# Power.net
KiCad netlist of a schematic drawn in Altium Designer
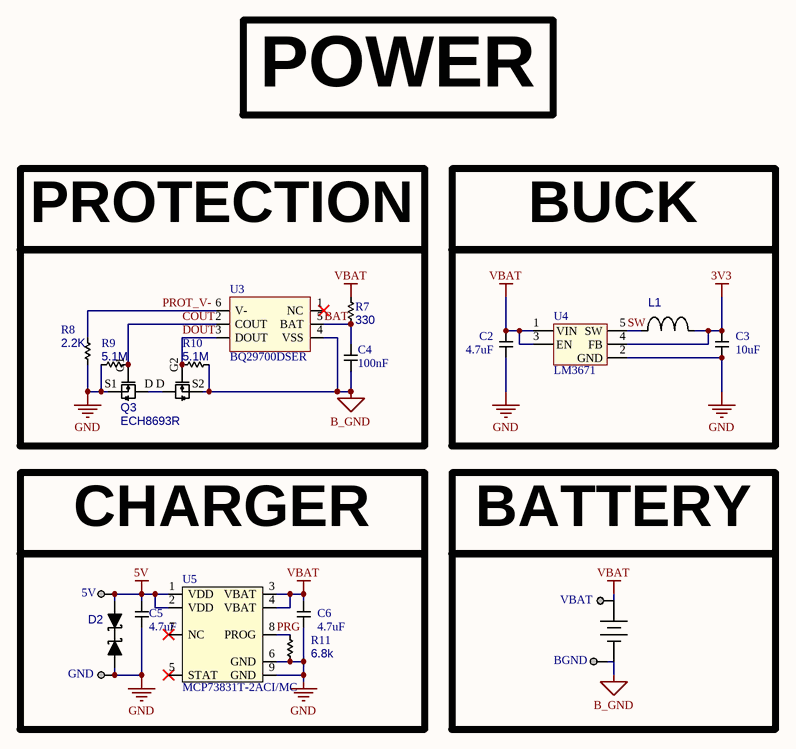
[diagram p0: Power.SchDoc]

(export (version "E")
  (design (tool "Eeschema 10.0.6"))
  (components
    (comp (ref "5V")
      (value "0.1\" Header")
      (footprint "0.1\" Header")
      (libsource (lib "smLib") (part "0.1{dblquote} Header"))
    )
    (comp (ref "BGND")
      (value "0.1\" Header")
      (footprint "0.1\" Header")
      (libsource (lib "smLib") (part "0.1{dblquote} Header"))
    )
    (comp (ref "C2")
      (value "4.7uF")
      (footprint "CAP_0402_HIGH")
      (description "0402 Capacitor")
      (libsource (lib "smLib") (part "Capacitor_0402"))
    )
    (comp (ref "C3")
      (value "10uF")
      (footprint "CAP_0402_HIGH")
      (description "0402 Capacitor")
      (libsource (lib "smLib") (part "Capacitor_0402"))
    )
    (comp (ref "C4")
      (value "100nF")
      (footprint "CAP_0402_HIGH")
      (description "0402 Capacitor")
      (libsource (lib "smLib") (part "Capacitor_0402"))
    )
    (comp (ref "C5")
      (value "4.7uF")
      (footprint "CAP_0402_HIGH")
      (description "0402 Capacitor")
      (libsource (lib "smLib") (part "Capacitor_0402"))
    )
    (comp (ref "C6")
      (value "4.7uF")
      (footprint "CAP_0402_HIGH")
      (description "0402 Capacitor")
      (libsource (lib "smLib") (part "Capacitor_0402"))
    )
    (comp (ref "D2")
      (value "D5V0L1B2LP4-7B")
      (footprint "D5V0L1B2LP4-7B")
      (description "D5V0L1B2LP4-7B 14V Clamp 6A (8/20µs) Ipp Tvs Diode Surface Mount X2-DFN1006-2")
      (libsource (lib "smLib") (part "D5V0L1B2LP4-7B"))
    )
    (comp (ref "GND")
      (value "0.1\" Header")
      (footprint "0.1\" Header")
      (libsource (lib "smLib") (part "0.1{dblquote} Header"))
    )
    (comp (ref "L1")
      (value "CIGT201610EH2R2MNE")
      (footprint "CIGT201610EH2R2MNE")
      (description "CIGT201610EH2R2MNE 2.2µH Unshielded Thin Film Inductor 2.5A 87mOhm Max 0806 (2016 Metric)")
      (libsource (lib "smLib") (part "CIGT201610EH2R2MNE"))
    )
    (comp (ref "Q3")
      (value "ECH8693R")
      (footprint "ECH8693R")
      (description "Mosfet Array 2 N-Channel (Dual) Common Drain 24V 14A 1.4W Surface Mount SOT-28FL/ECH8")
      (libsource (lib "smLib") (part "ECH8693R"))
    )
    (comp (ref "R7")
      (value "330")
      (footprint "RES_0402_HIGH")
      (description "0402 Resistor")
      (libsource (lib "smLib") (part "Resistor_0402"))
    )
    (comp (ref "R8")
      (value "2.2K")
      (footprint "RES_0402_HIGH")
      (description "0402 Resistor")
      (libsource (lib "smLib") (part "Resistor_0402"))
    )
    (comp (ref "R9")
      (value "5.1M")
      (footprint "RES_0402_HIGH")
      (description "0402 Resistor")
      (libsource (lib "smLib") (part "Resistor_0402"))
    )
    (comp (ref "R10")
      (value "5.1M")
      (footprint "RES_0402_HIGH")
      (description "0402 Resistor")
      (libsource (lib "smLib") (part "Resistor_0402"))
    )
    (comp (ref "R11")
      (value "6.8k")
      (footprint "RES_0402_HIGH")
      (description "0402 Resistor")
      (libsource (lib "smLib") (part "Resistor_0402"))
    )
    (comp (ref "U3")
      (value "BQ29700DSER")
      (footprint "BQ29700DSER")
      (description "Battery Battery Protection IC Lithium-Ion/Polymer 6-WSON (1.5x1.5)")
      (libsource (lib "smLib") (part "BQ29700DSER"))
    )
    (comp (ref "U4")
      (value "LM3671")
      (footprint "LM3671-BGA")
      (description "LM3671 IC REG BUCK 3.3V 0.6A SYNC 5USMD")
      (libsource (lib "smLib") (part "LM3671"))
    )
    (comp (ref "U5")
      (value "MCP73831T-2ACI/MC")
      (footprint "MCP73831T-2ACI/MC")
      (description "MCP73831T-2ACI/MC Charger IC Lithium-Ion/Polymer")
      (libsource (lib "smLib") (part "MCP73831T-2ACI/MC"))
    )
    (comp (ref "VBAT")
      (value "0.1\" Header")
      (footprint "0.1\" Header")
      (libsource (lib "smLib") (part "0.1{dblquote} Header"))
    )
  )
  (nets
    (net (code "1") (name "/BAT") (class "Default")
      (node (ref "C4") (pin "2") (pinfunction "2_2") (pintype "passive"))
      (node (ref "R7") (pin "2") (pinfunction "2_2") (pintype "passive"))
      (node (ref "U3") (pin "5") (pinfunction "BAT_5") (pintype "passive"))
    )
    (net (code "2") (name "/COUT") (class "Default")
      (node (ref "Q3") (pin "G1") (pinfunction "G_G1") (pintype "passive"))
      (node (ref "R9") (pin "1") (pinfunction "1_1") (pintype "passive"))
      (node (ref "U3") (pin "2") (pinfunction "COUT_2") (pintype "passive"))
    )
    (net (code "3") (name "/DOUT") (class "Default")
      (node (ref "Q3") (pin "G2") (pinfunction "G_G2") (pintype "passive"))
      (node (ref "R10") (pin "2") (pinfunction "2_2") (pintype "passive"))
      (node (ref "U3") (pin "3") (pinfunction "DOUT_3") (pintype "passive"))
    )
    (net (code "4") (name "/PRG") (class "Default")
      (node (ref "R11") (pin "1") (pinfunction "1_1") (pintype "passive"))
      (node (ref "U5") (pin "8") (pinfunction "PROG_8") (pintype "passive"))
    )
    (net (code "5") (name "/PROT_V-") (class "Default")
      (node (ref "R8") (pin "2") (pinfunction "2_2") (pintype "passive"))
      (node (ref "U3") (pin "6") (pinfunction "V-_6") (pintype "passive"))
    )
    (net (code "6") (name "/SW") (class "Default")
      (node (ref "L1") (pin "1") (pinfunction "1_1") (pintype "passive"))
      (node (ref "U4") (pin "5") (pinfunction "SW_5") (pintype "passive"))
    )
    (net (code "7") (name "3V3") (class "Default")
      (node (ref "C3") (pin "2") (pinfunction "2_2") (pintype "passive"))
      (node (ref "L1") (pin "2") (pinfunction "2_2") (pintype "passive"))
      (node (ref "U4") (pin "4") (pinfunction "FB_4") (pintype "passive"))
    )
    (net (code "8") (name "5V") (class "Default")
      (node (ref "5V") (pin "1") (pinfunction "1_1") (pintype "passive"))
      (node (ref "C5") (pin "2") (pinfunction "2_2") (pintype "passive"))
      (node (ref "D2") (pin "1") (pinfunction "1_1") (pintype "passive"))
      (node (ref "U5") (pin "1") (pinfunction "VDD_1") (pintype "passive"))
      (node (ref "U5") (pin "2") (pinfunction "VDD_2") (pintype "passive"))
    )
    (net (code "9") (name "B_GND") (class "Default")
      (node (ref "BGND") (pin "1") (pinfunction "1_1") (pintype "passive"))
      (node (ref "C4") (pin "1") (pinfunction "1_1") (pintype "passive"))
      (node (ref "Q3") (pin "S2") (pinfunction "S_S2") (pintype "passive"))
      (node (ref "R10") (pin "1") (pinfunction "1_1") (pintype "passive"))
      (node (ref "U3") (pin "4") (pinfunction "VSS_4") (pintype "passive"))
    )
    (net (code "10") (name "GND") (class "Default")
      (node (ref "C2") (pin "1") (pinfunction "1_1") (pintype "passive"))
      (node (ref "C3") (pin "1") (pinfunction "1_1") (pintype "passive"))
      (node (ref "C5") (pin "1") (pinfunction "1_1") (pintype "passive"))
      (node (ref "C6") (pin "1") (pinfunction "1_1") (pintype "passive"))
      (node (ref "D2") (pin "2") (pinfunction "2_2") (pintype "passive"))
      (node (ref "GND") (pin "1") (pinfunction "1_1") (pintype "passive"))
      (node (ref "Q3") (pin "S1") (pinfunction "S_S1") (pintype "passive"))
      (node (ref "R11") (pin "2") (pinfunction "2_2") (pintype "passive"))
      (node (ref "R8") (pin "1") (pinfunction "1_1") (pintype "passive"))
      (node (ref "R9") (pin "2") (pinfunction "2_2") (pintype "passive"))
      (node (ref "U4") (pin "2") (pinfunction "GND_2") (pintype "passive"))
      (node (ref "U5") (pin "6") (pinfunction "GND_6") (pintype "passive"))
      (node (ref "U5") (pin "9") (pinfunction "GND_9") (pintype "passive"))
    )
    (net (code "11") (name "Net-(Q3-PadD)") (class "Default")
      (node (ref "Q3") (pin "D") (pinfunction "D_D") (pintype "passive"))
    )
    (net (code "12") (name "VBAT") (class "Default")
      (node (ref "C2") (pin "2") (pinfunction "2_2") (pintype "passive"))
      (node (ref "C6") (pin "2") (pinfunction "2_2") (pintype "passive"))
      (node (ref "R7") (pin "1") (pinfunction "1_1") (pintype "passive"))
      (node (ref "U4") (pin "1") (pinfunction "VIN_1") (pintype "passive"))
      (node (ref "U4") (pin "3") (pinfunction "EN_3") (pintype "passive"))
      (node (ref "U5") (pin "3") (pinfunction "VBAT_3") (pintype "passive"))
      (node (ref "U5") (pin "4") (pinfunction "VBAT_4") (pintype "passive"))
      (node (ref "VBAT") (pin "1") (pinfunction "1_1") (pintype "passive"))
    )
    (net (code "13") (name "unconnected-(U3-NC-Pad1)") (class "Default")
      (node (ref "U3") (pin "1") (pinfunction "NC_1") (pintype "passive+no_connect"))
    )
    (net (code "14") (name "unconnected-(U5-NC-Pad7)") (class "Default")
      (node (ref "U5") (pin "7") (pinfunction "NC_7") (pintype "passive+no_connect"))
    )
    (net (code "15") (name "unconnected-(U5-STAT-Pad5)") (class "Default")
      (node (ref "U5") (pin "5") (pinfunction "STAT_5") (pintype "passive+no_connect"))
    )
  )
)
